# Sheet1.net
KiCad netlist of a schematic drawn in Altium Designer
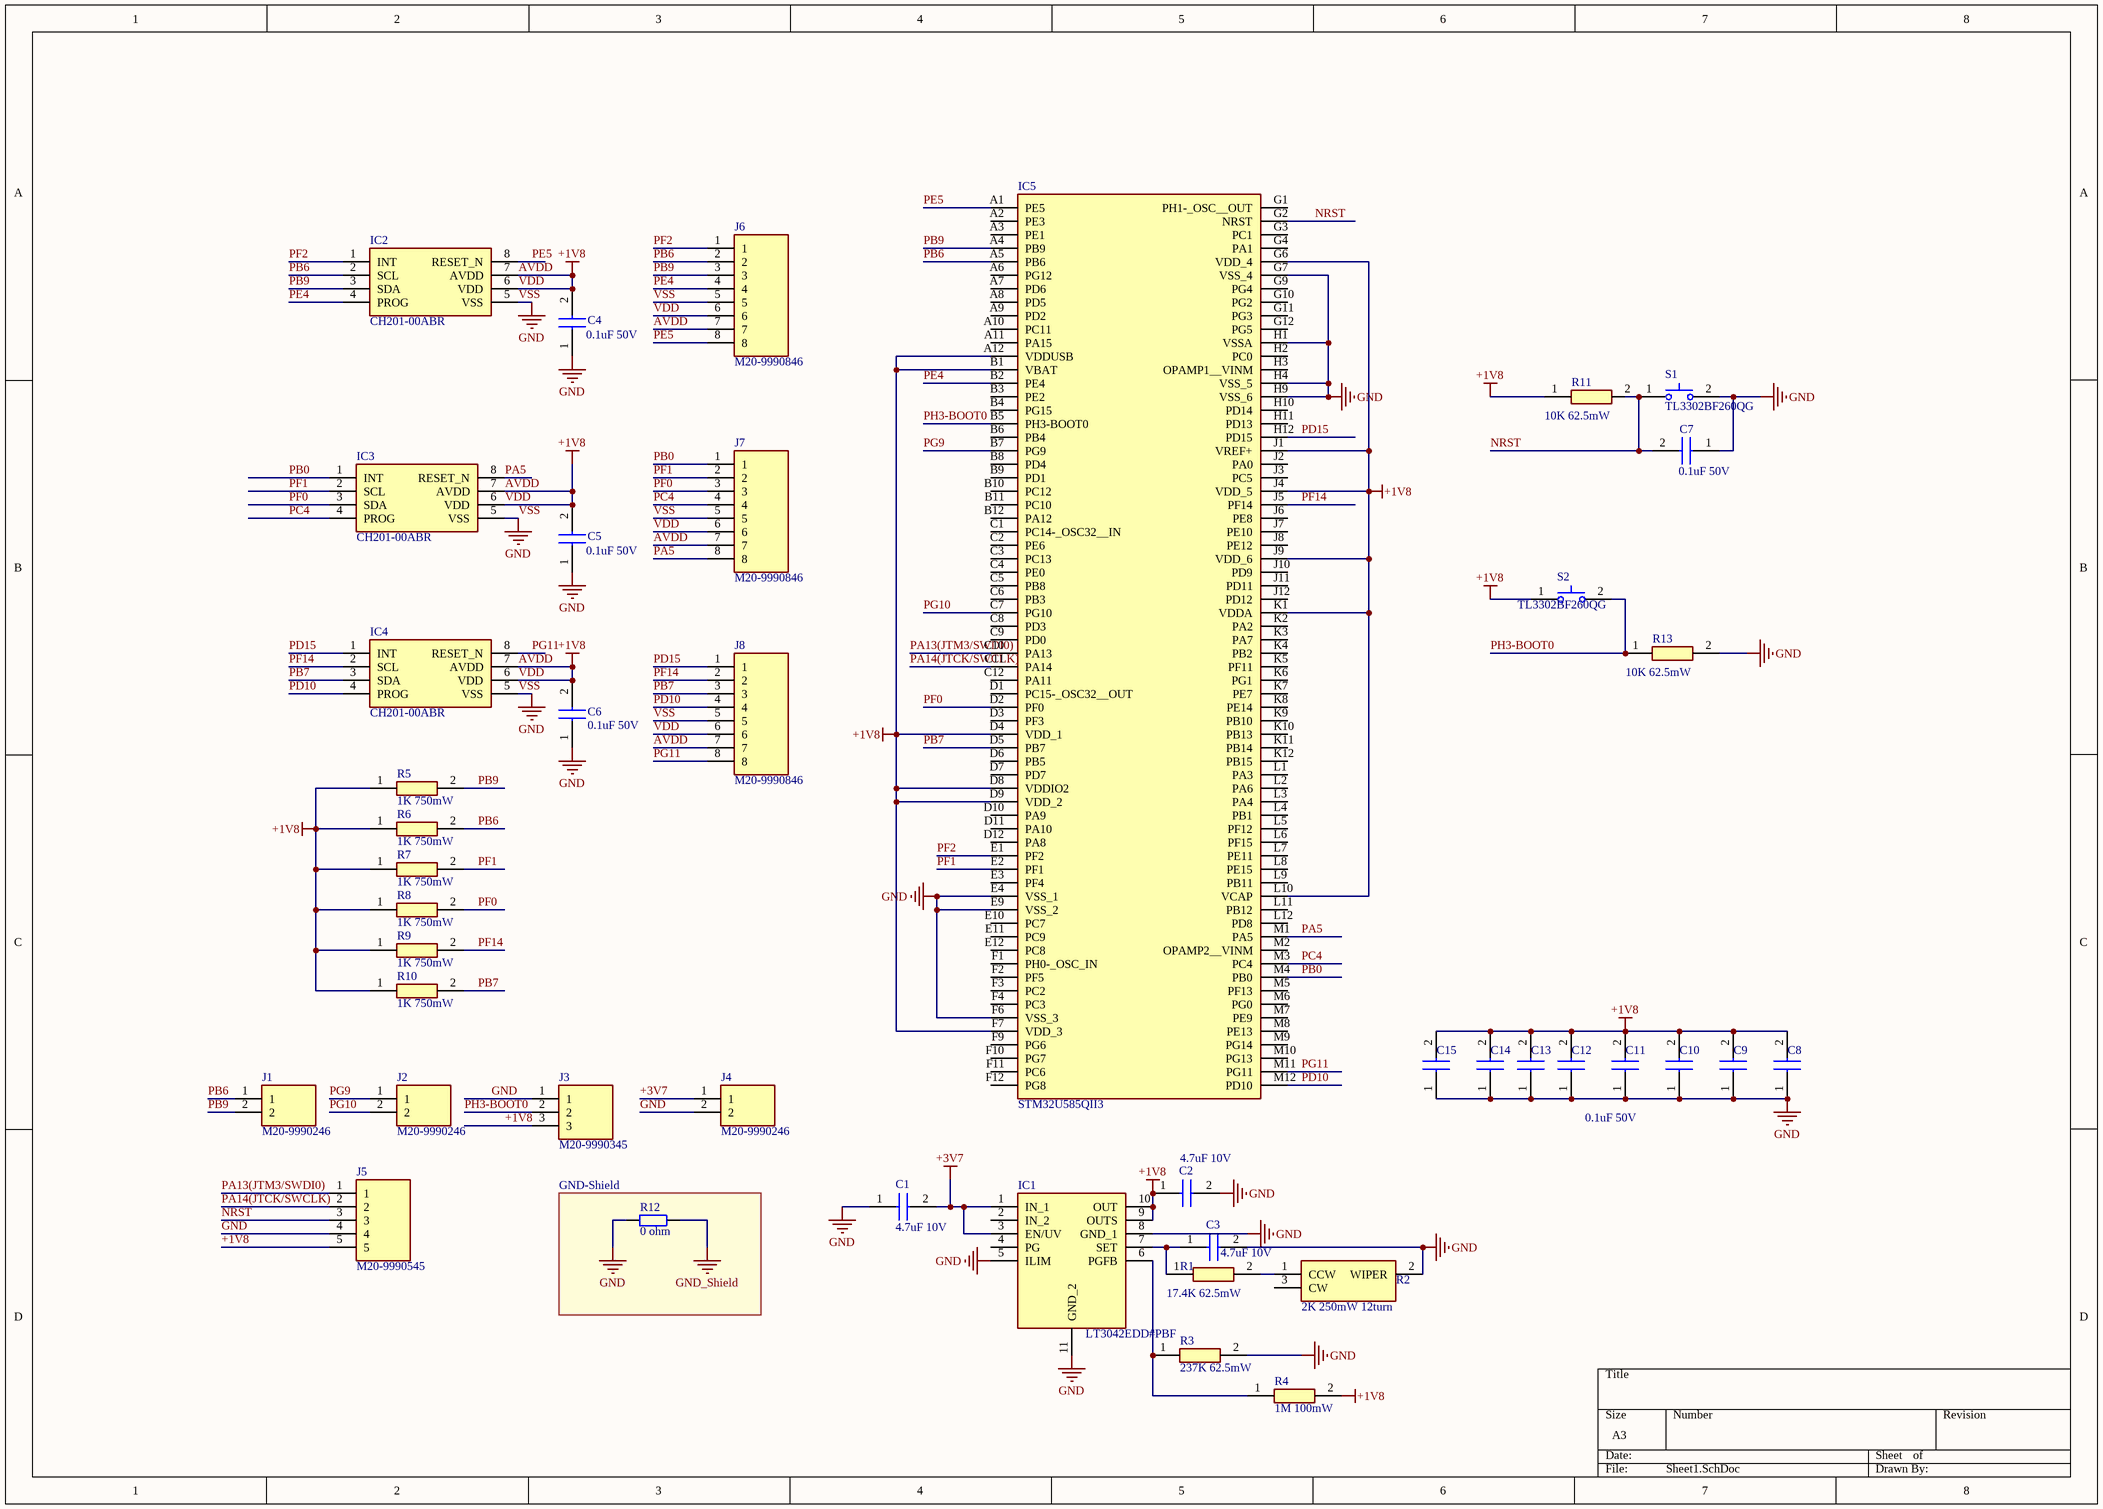
[diagram p0: Sheet1.SchDoc]

(export (version "E")
  (design (tool "Eeschema 10.0.6"))
  (components
    (comp (ref "C1")
      (value "4.7uF 10V")
      (footprint "SamacSys:CAPC3225X220N")
      (description "Capacitor")
      (fields (field (name "MANUFACTURER_PART_NUMBER") "1210X475K100CT"))
      (libsource (lib "*") (part "1210X475K100CT"))
    )
    (comp (ref "C2")
      (value "4.7uF 10V")
      (footprint "SamacSys:CAPC3225X220N")
      (description "Capacitor")
      (fields (field (name "MANUFACTURER_PART_NUMBER") "1210X475K100CT"))
      (libsource (lib "*") (part "1210X475K100CT"))
    )
    (comp (ref "C3")
      (value "4.7uF 10V")
      (footprint "SamacSys:CAPC3225X220N")
      (description "Capacitor")
      (fields (field (name "MANUFACTURER_PART_NUMBER") "1210X475K100CT"))
      (libsource (lib "*") (part "1210X475K100CT"))
    )
    (comp (ref "C4")
      (value "0.1uF 50V")
      (footprint "SamacSys:CAPC1608X90N")
      (description "Capacitor")
      (fields
        (field (name "MANUFACTURER_PART_NUMBER") "CC0603KRX7R9BB104")
        (field (name "MOUSER PART NUMBER") "603-CC603KRX7R9BB104")
      )
      (libsource (lib "SamacSys") (part "CC0603KRX7R9BB104"))
    )
    (comp (ref "C5")
      (value "0.1uF 50V")
      (footprint "SamacSys:CAPC1608X90N")
      (description "Capacitor")
      (fields
        (field (name "MANUFACTURER_PART_NUMBER") "CC0603KRX7R9BB104")
        (field (name "MOUSER PART NUMBER") "603-CC603KRX7R9BB104")
      )
      (libsource (lib "*") (part "CC0603KRX7R9BB104"))
    )
    (comp (ref "C6")
      (value "0.1uF 50V")
      (footprint "SamacSys:CAPC1608X90N")
      (description "Capacitor")
      (fields
        (field (name "MANUFACTURER_PART_NUMBER") "CC0603KRX7R9BB104")
        (field (name "MOUSER PART NUMBER") "603-CC603KRX7R9BB104")
      )
      (libsource (lib "SamacSys") (part "CC0603KRX7R9BB104"))
    )
    (comp (ref "C7")
      (value "0.1uF 50V")
      (footprint "SamacSys:CAPC1608X90N")
      (description "Capacitor")
      (fields
        (field (name "MANUFACTURER_PART_NUMBER") "CC0603KRX7R9BB104")
        (field (name "MOUSER PART NUMBER") "603-CC603KRX7R9BB104")
      )
      (libsource (lib "SamacSys") (part "CC0603KRX7R9BB104"))
    )
    (comp (ref "C8")
      (value "CC0603KRX7R9BB104")
      (footprint "SamacSys:CAPC1608X90N")
      (description "Capacitor")
      (fields (field (name "MOUSER PART NUMBER") "603-CC603KRX7R9BB104"))
      (libsource (lib "SamacSys") (part "CC0603KRX7R9BB104"))
    )
    (comp (ref "C9")
      (value "CC0603KRX7R9BB104")
      (footprint "SamacSys:CAPC1608X90N")
      (description "Capacitor")
      (fields (field (name "MOUSER PART NUMBER") "603-CC603KRX7R9BB104"))
      (libsource (lib "SamacSys") (part "CC0603KRX7R9BB104"))
    )
    (comp (ref "C10")
      (value "CC0603KRX7R9BB104")
      (footprint "SamacSys:CAPC1608X90N")
      (description "Capacitor")
      (fields (field (name "MOUSER PART NUMBER") "603-CC603KRX7R9BB104"))
      (libsource (lib "SamacSys") (part "CC0603KRX7R9BB104"))
    )
    (comp (ref "C11")
      (value "0.1uF 50V")
      (footprint "SamacSys:CAPC1608X90N")
      (description "Capacitor")
      (fields
        (field (name "MANUFACTURER_PART_NUMBER") "CC0603KRX7R9BB104")
        (field (name "MOUSER PART NUMBER") "603-CC603KRX7R9BB104")
      )
      (libsource (lib "SamacSys") (part "CC0603KRX7R9BB104"))
    )
    (comp (ref "C12")
      (value "CC0603KRX7R9BB104")
      (footprint "SamacSys:CAPC1608X90N")
      (description "Capacitor")
      (fields (field (name "MOUSER PART NUMBER") "603-CC603KRX7R9BB104"))
      (libsource (lib "SamacSys") (part "CC0603KRX7R9BB104"))
    )
    (comp (ref "C13")
      (value "CC0603KRX7R9BB104")
      (footprint "SamacSys:CAPC1608X90N")
      (description "Capacitor")
      (fields (field (name "MOUSER PART NUMBER") "603-CC603KRX7R9BB104"))
      (libsource (lib "SamacSys") (part "CC0603KRX7R9BB104"))
    )
    (comp (ref "C14")
      (value "CC0603KRX7R9BB104")
      (footprint "SamacSys:CAPC1608X90N")
      (description "Capacitor")
      (fields (field (name "MOUSER PART NUMBER") "603-CC603KRX7R9BB104"))
      (libsource (lib "SamacSys") (part "CC0603KRX7R9BB104"))
    )
    (comp (ref "C15")
      (value "CC0603KRX7R9BB104")
      (footprint "SamacSys:CAPC1608X90N")
      (description "Capacitor")
      (fields (field (name "MOUSER PART NUMBER") "603-CC603KRX7R9BB104"))
      (libsource (lib "SamacSys") (part "CC0603KRX7R9BB104"))
    )
    (comp (ref "IC1")
      (value "LT3042EDD#PBF")
      (footprint "SamacSys:SON50P300X300X80-11N-D")
      (description "Integrated Circuit")
      (fields (field (name "MOUSER PART NUMBER") "584-LT3042EDD#PBF"))
      (libsource (lib "SamacSys") (part "LT3042EDD#PBF"))
    )
    (comp (ref "IC2")
      (value "CH201-00ABR")
      (footprint "SamacSys:CH20100ABR")
      (description "Filter")
      (fields (field (name "MOUSER PART NUMBER") "410-CH201-00ABR"))
      (libsource (lib "SamacSys") (part "CH201-00ABR"))
    )
    (comp (ref "IC3")
      (value "CH201-00ABR")
      (footprint "SamacSys:CH20100ABR")
      (description "Filter")
      (fields (field (name "MOUSER PART NUMBER") "410-CH201-00ABR"))
      (libsource (lib "SamacSys") (part "CH201-00ABR"))
    )
    (comp (ref "IC4")
      (value "CH201-00ABR")
      (footprint "SamacSys:CH20100ABR")
      (description "Filter")
      (fields (field (name "MOUSER PART NUMBER") "410-CH201-00ABR"))
      (libsource (lib "SamacSys") (part "CH201-00ABR"))
    )
    (comp (ref "IC5")
      (value "STM32U585QII3")
      (footprint "SamacSys:STM32U585QII3")
      (description "Integrated Circuit")
      (fields (field (name "MOUSER PART NUMBER") "511-STM32U585QII3"))
      (libsource (lib "SamacSys") (part "STM32U585QII3"))
    )
    (comp (ref "J1")
      (value "M20-9990246")
      (footprint "SamacSys:HDRV2W66P0X254_1X2_508X254X874P")
      (description "Connector")
      (fields (field (name "MOUSER PART NUMBER") "855-M20-9990246"))
      (libsource (lib "SamacSys") (part "M20-9990246"))
    )
    (comp (ref "J2")
      (value "M20-9990246")
      (footprint "SamacSys:HDRV2W66P0X254_1X2_508X254X874P")
      (description "Connector")
      (fields (field (name "MOUSER PART NUMBER") "855-M20-9990246"))
      (libsource (lib "SamacSys") (part "M20-9990246"))
    )
    (comp (ref "J3")
      (value "M20-9990345")
      (footprint "SamacSys:HDRV3W64P0X254_1X3_762X254X864P")
      (description "Connector")
      (fields (field (name "MOUSER PART NUMBER") "855-M20-9990345"))
      (libsource (lib "SamacSys") (part "M20-9990345"))
    )
    (comp (ref "J4")
      (value "M20-9990246")
      (footprint "SamacSys:HDRV2W66P0X254_1X2_508X254X874P")
      (description "Connector")
      (fields (field (name "MOUSER PART NUMBER") "855-M20-9990246"))
      (libsource (lib "SamacSys") (part "M20-9990246"))
    )
    (comp (ref "J5")
      (value "M20-9990545")
      (footprint "SamacSys:HDRV5W64P0X254_1X5_1270X254X864P")
      (description "Connector")
      (fields (field (name "MOUSER PART NUMBER") "855-M20-9990545"))
      (libsource (lib "*") (part "M20-9990545"))
    )
    (comp (ref "J6")
      (value "M20-9990846")
      (footprint "SamacSys:HDRV8W66P0X254_1X8_2032X254X860P")
      (description "Connector")
      (fields (field (name "MOUSER PART NUMBER") "855-M20-9990846"))
      (libsource (lib "SamacSys") (part "M20-9990846"))
    )
    (comp (ref "J7")
      (value "M20-9990846")
      (footprint "SamacSys:HDRV8W66P0X254_1X8_2032X254X860P")
      (description "Connector")
      (fields (field (name "MOUSER PART NUMBER") "855-M20-9990846"))
      (libsource (lib "SamacSys") (part "M20-9990846"))
    )
    (comp (ref "J8")
      (value "M20-9990846")
      (footprint "SamacSys:HDRV8W66P0X254_1X8_2032X254X860P")
      (description "Connector")
      (fields (field (name "MOUSER PART NUMBER") "855-M20-9990846"))
      (libsource (lib "SamacSys") (part "M20-9990846"))
    )
    (comp (ref "R1")
      (value "17.4K 62.5mW")
      (footprint "SamacSys:RESC1005X40N")
      (description "Resistor")
      (fields
        (field (name "MANUFACTURER_PART_NUMBER") "CR0402-FX-1742GLF")
        (field (name "MOUSER PART NUMBER") "652-CR0402-FX1742GLF")
      )
      (libsource (lib "*") (part "CR0402-FX-1742GLF"))
    )
    (comp (ref "R2")
      (value "2K 250mW 12turn")
      (footprint "SamacSys:3224W1202G")
      (description "Variable Resistor")
      (fields
        (field (name "MANUFACTURER_PART_NUMBER") "3224W-1-202G")
        (field (name "MOUSER PART NUMBER") "652-3224W-1-202G")
      )
      (libsource (lib "*") (part "3224W-1-202G"))
    )
    (comp (ref "R3")
      (value "237K 62.5mW")
      (footprint "SamacSys:RESC1005X40N")
      (description "Resistor")
      (fields
        (field (name "MANUFACTURER_PART_NUMBER") "CR0402-FX-2373GLF")
        (field (name "MOUSER PART NUMBER") "652-CR0402FX2373GLF")
      )
      (libsource (lib "*") (part "CR0402-FX-2373GLF"))
    )
    (comp (ref "R4")
      (value "1M 100mW")
      (footprint "SamacSys:RESC1005X37N")
      (description "Resistor")
      (fields
        (field (name "MANUFACTURER_PART_NUMBER") "MCS0402MD1004BE000")
        (field (name "MOUSER PART NUMBER") "594-MCS0402MD1004BE0")
      )
      (libsource (lib "*") (part "MCS0402MD1004BE000"))
    )
    (comp (ref "R5")
      (value "1K 750mW")
      (footprint "SamacSys:RESC1632X65N")
      (description "Resistor")
      (fields
        (field (name "MANUFACTURER_PART_NUMBER") "LTR18EZPF1001")
        (field (name "MOUSER PART NUMBER") "755-LTR18EZPF1001")
      )
      (libsource (lib "*") (part "LTR18EZPF1001"))
    )
    (comp (ref "R6")
      (value "1K 750mW")
      (footprint "SamacSys:RESC1632X65N")
      (description "Resistor")
      (fields
        (field (name "MANUFACTURER_PART_NUMBER") "LTR18EZPF1001")
        (field (name "MOUSER PART NUMBER") "755-LTR18EZPF1001")
      )
      (libsource (lib "*") (part "LTR18EZPF1001"))
    )
    (comp (ref "R7")
      (value "1K 750mW")
      (footprint "SamacSys:RESC1632X65N")
      (description "Resistor")
      (fields
        (field (name "MANUFACTURER_PART_NUMBER") "LTR18EZPF1001")
        (field (name "MOUSER PART NUMBER") "755-LTR18EZPF1001")
      )
      (libsource (lib "*") (part "LTR18EZPF1001"))
    )
    (comp (ref "R8")
      (value "1K 750mW")
      (footprint "SamacSys:RESC1632X65N")
      (description "Resistor")
      (fields
        (field (name "MANUFACTURER_PART_NUMBER") "LTR18EZPF1001")
        (field (name "MOUSER PART NUMBER") "755-LTR18EZPF1001")
      )
      (libsource (lib "*") (part "LTR18EZPF1001"))
    )
    (comp (ref "R9")
      (value "1K 750mW")
      (footprint "SamacSys:RESC1632X65N")
      (description "Resistor")
      (fields
        (field (name "MANUFACTURER_PART_NUMBER") "LTR18EZPF1001")
        (field (name "MOUSER PART NUMBER") "755-LTR18EZPF1001")
      )
      (libsource (lib "*") (part "LTR18EZPF1001"))
    )
    (comp (ref "R10")
      (value "1K 750mW")
      (footprint "SamacSys:RESC1632X65N")
      (description "Resistor")
      (fields
        (field (name "MANUFACTURER_PART_NUMBER") "LTR18EZPF1001")
        (field (name "MOUSER PART NUMBER") "755-LTR18EZPF1001")
      )
      (libsource (lib "*") (part "LTR18EZPF1001"))
    )
    (comp (ref "R11")
      (value "10K 62.5mW")
      (footprint "SamacSys:RESC1005X40N")
      (description "Resistor")
      (fields
        (field (name "MANUFACTURER_PART_NUMBER") "SFR01MZPF1002")
        (field (name "MOUSER PART NUMBER") "755-SFR01MZPF1002")
      )
      (libsource (lib "*") (part "SFR01MZPF1002"))
    )
    (comp (ref "R12")
      (value "0 ohm")
      (footprint "jumper_2.54")
      (description "Resistor")
      (fields (field (name "PUBLISHER") "Altium Limited"))
      (libsource (lib "Miscellaneous Devices") (part "Res2"))
    )
    (comp (ref "R13")
      (value "10K 62.5mW")
      (footprint "SamacSys:RESC1005X40N")
      (description "Resistor")
      (fields
        (field (name "MANUFACTURER_PART_NUMBER") "SFR01MZPF1002")
        (field (name "MOUSER PART NUMBER") "755-SFR01MZPF1002")
      )
      (libsource (lib "*") (part "SFR01MZPF1002"))
    )
    (comp (ref "S1")
      (value "TL3302BF260QG")
      (footprint "SamacSys:TL3302BF260QG")
      (description "Switch (2-Pin Push)")
      (fields (field (name "MOUSER PART NUMBER") "612-TL3302BF260QG"))
      (libsource (lib "*") (part "TL3302BF260QG"))
    )
    (comp (ref "S2")
      (value "TL3302BF260QG")
      (footprint "SamacSys:TL3302BF260QG")
      (description "Switch (2-Pin Push)")
      (fields (field (name "MOUSER PART NUMBER") "612-TL3302BF260QG"))
      (libsource (lib "*") (part "TL3302BF260QG"))
    )
  )
  (nets
    (net (code "1") (name "+1V8") (class "Default")
      (node (ref "C10") (pin "2") (pinfunction "2_2") (pintype "passive"))
      (node (ref "C11") (pin "2") (pinfunction "2_2") (pintype "passive"))
      (node (ref "C12") (pin "2") (pinfunction "2_2") (pintype "passive"))
      (node (ref "C13") (pin "2") (pinfunction "2_2") (pintype "passive"))
      (node (ref "C14") (pin "2") (pinfunction "2_2") (pintype "passive"))
      (node (ref "C15") (pin "2") (pinfunction "2_2") (pintype "passive"))
      (node (ref "C2") (pin "1") (pinfunction "1_1") (pintype "passive"))
      (node (ref "C4") (pin "2") (pinfunction "2_2") (pintype "passive"))
      (node (ref "C5") (pin "2") (pinfunction "2_2") (pintype "passive"))
      (node (ref "C6") (pin "2") (pinfunction "2_2") (pintype "passive"))
      (node (ref "C8") (pin "2") (pinfunction "2_2") (pintype "passive"))
      (node (ref "C9") (pin "2") (pinfunction "2_2") (pintype "passive"))
      (node (ref "IC1") (pin "10") (pinfunction "OUT_10") (pintype "passive"))
      (node (ref "IC1") (pin "9") (pinfunction "OUTS_9") (pintype "passive"))
      (node (ref "IC2") (pin "6") (pinfunction "VDD_6") (pintype "passive"))
      (node (ref "IC2") (pin "7") (pinfunction "AVDD_7") (pintype "passive"))
      (node (ref "IC3") (pin "6") (pinfunction "VDD_6") (pintype "passive"))
      (node (ref "IC3") (pin "7") (pinfunction "AVDD_7") (pintype "passive"))
      (node (ref "IC4") (pin "6") (pinfunction "VDD_6") (pintype "passive"))
      (node (ref "IC4") (pin "7") (pinfunction "AVDD_7") (pintype "passive"))
      (node (ref "IC5") (pin "A12") (pinfunction "VDDUSB_A12") (pintype "passive"))
      (node (ref "IC5") (pin "B1") (pinfunction "VBAT_B1") (pintype "passive"))
      (node (ref "IC5") (pin "D4") (pinfunction "VDD_1_D4") (pintype "passive"))
      (node (ref "IC5") (pin "D8") (pinfunction "VDDIO2_D8") (pintype "passive"))
      (node (ref "IC5") (pin "D9") (pinfunction "VDD_2_D9") (pintype "passive"))
      (node (ref "IC5") (pin "F7") (pinfunction "VDD_3_F7") (pintype "passive"))
      (node (ref "IC5") (pin "G6") (pinfunction "VDD_4_G6") (pintype "passive"))
      (node (ref "IC5") (pin "J1") (pinfunction "VREF+_J1") (pintype "passive"))
      (node (ref "IC5") (pin "J4") (pinfunction "VDD_5_J4") (pintype "passive"))
      (node (ref "IC5") (pin "J9") (pinfunction "VDD_6_J9") (pintype "passive"))
      (node (ref "IC5") (pin "K1") (pinfunction "VDDA_K1") (pintype "passive"))
      (node (ref "IC5") (pin "L10") (pinfunction "VCAP_L10") (pintype "passive"))
      (node (ref "J3") (pin "3") (pinfunction "3_3") (pintype "passive"))
      (node (ref "J5") (pin "5") (pinfunction "5_5") (pintype "passive"))
      (node (ref "J6") (pin "6") (pinfunction "6_6") (pintype "passive"))
      (node (ref "J6") (pin "7") (pinfunction "7_7") (pintype "passive"))
      (node (ref "J7") (pin "6") (pinfunction "6_6") (pintype "passive"))
      (node (ref "J7") (pin "7") (pinfunction "7_7") (pintype "passive"))
      (node (ref "J8") (pin "6") (pinfunction "6_6") (pintype "passive"))
      (node (ref "J8") (pin "7") (pinfunction "7_7") (pintype "passive"))
      (node (ref "R10") (pin "1") (pinfunction "1_1") (pintype "passive"))
      (node (ref "R11") (pin "1") (pinfunction "1_1") (pintype "passive"))
      (node (ref "R4") (pin "2") (pinfunction "2_2") (pintype "passive"))
      (node (ref "R5") (pin "1") (pinfunction "1_1") (pintype "passive"))
      (node (ref "R6") (pin "1") (pinfunction "1_1") (pintype "passive"))
      (node (ref "R7") (pin "1") (pinfunction "1_1") (pintype "passive"))
      (node (ref "R8") (pin "1") (pinfunction "1_1") (pintype "passive"))
      (node (ref "R9") (pin "1") (pinfunction "1_1") (pintype "passive"))
      (node (ref "S2") (pin "1") (pinfunction "COM_1") (pintype "passive"))
    )
    (net (code "2") (name "+3V7") (class "Default")
      (node (ref "C1") (pin "2") (pinfunction "2_2") (pintype "passive"))
      (node (ref "IC1") (pin "1") (pinfunction "IN_1_1") (pintype "passive"))
      (node (ref "IC1") (pin "3") (pinfunction "EN/UV_3") (pintype "passive"))
      (node (ref "J4") (pin "1") (pinfunction "1_1") (pintype "passive"))
    )
    (net (code "3") (name "/NRST") (class "Default")
      (node (ref "C7") (pin "2") (pinfunction "2_2") (pintype "passive"))
      (node (ref "IC5") (pin "G2") (pinfunction "NRST_G2") (pintype "passive"))
      (node (ref "J5") (pin "3") (pinfunction "3_3") (pintype "passive"))
      (node (ref "R11") (pin "2") (pinfunction "2_2") (pintype "passive"))
      (node (ref "S1") (pin "1") (pinfunction "COM_1") (pintype "passive"))
    )
    (net (code "4") (name "/PA5") (class "Default")
      (node (ref "IC3") (pin "8") (pinfunction "RESET_N_8") (pintype "passive"))
      (node (ref "IC5") (pin "M1") (pinfunction "PA5_M1") (pintype "passive"))
      (node (ref "J7") (pin "8") (pinfunction "8_8") (pintype "passive"))
    )
    (net (code "5") (name "/PA13(JTM3{slash}SWDI0)") (class "Default")
      (node (ref "IC5") (pin "C10") (pinfunction "PA13_C10") (pintype "passive"))
      (node (ref "J5") (pin "1") (pinfunction "1_1") (pintype "passive"))
    )
    (net (code "6") (name "/PA14(JTCK{slash}SWCLK)") (class "Default")
      (node (ref "IC5") (pin "C11") (pinfunction "PA14_C11") (pintype "passive"))
      (node (ref "J5") (pin "2") (pinfunction "2_2") (pintype "passive"))
    )
    (net (code "7") (name "/PB0") (class "Default")
      (node (ref "IC3") (pin "1") (pinfunction "INT_1") (pintype "passive"))
      (node (ref "IC5") (pin "M4") (pinfunction "PB0_M4") (pintype "passive"))
      (node (ref "J7") (pin "1") (pinfunction "1_1") (pintype "passive"))
    )
    (net (code "8") (name "/PB6") (class "Default")
      (node (ref "IC2") (pin "2") (pinfunction "SCL_2") (pintype "passive"))
      (node (ref "IC5") (pin "A5") (pinfunction "PB6_A5") (pintype "passive"))
      (node (ref "J1") (pin "1") (pinfunction "1_1") (pintype "passive"))
      (node (ref "J6") (pin "2") (pinfunction "2_2") (pintype "passive"))
      (node (ref "R6") (pin "2") (pinfunction "2_2") (pintype "passive"))
    )
    (net (code "9") (name "/PB7") (class "Default")
      (node (ref "IC4") (pin "3") (pinfunction "SDA_3") (pintype "passive"))
      (node (ref "IC5") (pin "D5") (pinfunction "PB7_D5") (pintype "passive"))
      (node (ref "J8") (pin "3") (pinfunction "3_3") (pintype "passive"))
      (node (ref "R10") (pin "2") (pinfunction "2_2") (pintype "passive"))
    )
    (net (code "10") (name "/PB9") (class "Default")
      (node (ref "IC2") (pin "3") (pinfunction "SDA_3") (pintype "passive"))
      (node (ref "IC5") (pin "A4") (pinfunction "PB9_A4") (pintype "passive"))
      (node (ref "J1") (pin "2") (pinfunction "2_2") (pintype "passive"))
      (node (ref "J6") (pin "3") (pinfunction "3_3") (pintype "passive"))
      (node (ref "R5") (pin "2") (pinfunction "2_2") (pintype "passive"))
    )
    (net (code "11") (name "/PC4") (class "Default")
      (node (ref "IC3") (pin "4") (pinfunction "PROG_4") (pintype "passive"))
      (node (ref "IC5") (pin "M3") (pinfunction "PC4_M3") (pintype "passive"))
      (node (ref "J7") (pin "4") (pinfunction "4_4") (pintype "passive"))
    )
    (net (code "12") (name "/PD10") (class "Default")
      (node (ref "IC4") (pin "4") (pinfunction "PROG_4") (pintype "passive"))
      (node (ref "IC5") (pin "M12") (pinfunction "PD10_M12") (pintype "passive"))
      (node (ref "J8") (pin "4") (pinfunction "4_4") (pintype "passive"))
    )
    (net (code "13") (name "/PD15") (class "Default")
      (node (ref "IC4") (pin "1") (pinfunction "INT_1") (pintype "passive"))
      (node (ref "IC5") (pin "H12") (pinfunction "PD15_H12") (pintype "passive"))
      (node (ref "J8") (pin "1") (pinfunction "1_1") (pintype "passive"))
    )
    (net (code "14") (name "/PE4") (class "Default")
      (node (ref "IC2") (pin "4") (pinfunction "PROG_4") (pintype "passive"))
      (node (ref "IC5") (pin "B2") (pinfunction "PE4_B2") (pintype "passive"))
      (node (ref "J6") (pin "4") (pinfunction "4_4") (pintype "passive"))
    )
    (net (code "15") (name "/PE5") (class "Default")
      (node (ref "IC2") (pin "8") (pinfunction "RESET_N_8") (pintype "passive"))
      (node (ref "IC5") (pin "A1") (pinfunction "PE5_A1") (pintype "passive"))
      (node (ref "J6") (pin "8") (pinfunction "8_8") (pintype "passive"))
    )
    (net (code "16") (name "/PF0") (class "Default")
      (node (ref "IC3") (pin "3") (pinfunction "SDA_3") (pintype "passive"))
      (node (ref "IC5") (pin "D2") (pinfunction "PF0_D2") (pintype "passive"))
      (node (ref "J7") (pin "3") (pinfunction "3_3") (pintype "passive"))
      (node (ref "R8") (pin "2") (pinfunction "2_2") (pintype "passive"))
    )
    (net (code "17") (name "/PF1") (class "Default")
      (node (ref "IC3") (pin "2") (pinfunction "SCL_2") (pintype "passive"))
      (node (ref "IC5") (pin "E2") (pinfunction "PF1_E2") (pintype "passive"))
      (node (ref "J7") (pin "2") (pinfunction "2_2") (pintype "passive"))
      (node (ref "R7") (pin "2") (pinfunction "2_2") (pintype "passive"))
    )
    (net (code "18") (name "/PF2") (class "Default")
      (node (ref "IC2") (pin "1") (pinfunction "INT_1") (pintype "passive"))
      (node (ref "IC5") (pin "E1") (pinfunction "PF2_E1") (pintype "passive"))
      (node (ref "J6") (pin "1") (pinfunction "1_1") (pintype "passive"))
    )
    (net (code "19") (name "/PF14") (class "Default")
      (node (ref "IC4") (pin "2") (pinfunction "SCL_2") (pintype "passive"))
      (node (ref "IC5") (pin "J5") (pinfunction "PF14_J5") (pintype "passive"))
      (node (ref "J8") (pin "2") (pinfunction "2_2") (pintype "passive"))
      (node (ref "R9") (pin "2") (pinfunction "2_2") (pintype "passive"))
    )
    (net (code "20") (name "/PG9") (class "Default")
      (node (ref "IC5") (pin "B7") (pinfunction "PG9_B7") (pintype "passive"))
      (node (ref "J2") (pin "1") (pinfunction "1_1") (pintype "passive"))
    )
    (net (code "21") (name "/PG10") (class "Default")
      (node (ref "IC5") (pin "C7") (pinfunction "PG10_C7") (pintype "passive"))
      (node (ref "J2") (pin "2") (pinfunction "2_2") (pintype "passive"))
    )
    (net (code "22") (name "/PG11") (class "Default")
      (node (ref "IC4") (pin "8") (pinfunction "RESET_N_8") (pintype "passive"))
      (node (ref "IC5") (pin "M11") (pinfunction "PG11_M11") (pintype "passive"))
      (node (ref "J8") (pin "8") (pinfunction "8_8") (pintype "passive"))
    )
    (net (code "23") (name "/PH3-BOOT0") (class "Default")
      (node (ref "IC5") (pin "B5") (pinfunction "PH3-BOOT0_B5") (pintype "passive"))
      (node (ref "J3") (pin "2") (pinfunction "2_2") (pintype "passive"))
      (node (ref "R13") (pin "1") (pinfunction "1_1") (pintype "passive"))
      (node (ref "S2") (pin "2") (pinfunction "NO_2") (pintype "passive"))
    )
    (net (code "24") (name "GND") (class "Default")
      (node (ref "C1") (pin "1") (pinfunction "1_1") (pintype "passive"))
      (node (ref "C10") (pin "1") (pinfunction "1_1") (pintype "passive"))
      (node (ref "C11") (pin "1") (pinfunction "1_1") (pintype "passive"))
      (node (ref "C12") (pin "1") (pinfunction "1_1") (pintype "passive"))
      (node (ref "C13") (pin "1") (pinfunction "1_1") (pintype "passive"))
      (node (ref "C14") (pin "1") (pinfunction "1_1") (pintype "passive"))
      (node (ref "C15") (pin "1") (pinfunction "1_1") (pintype "passive"))
      (node (ref "C2") (pin "2") (pinfunction "2_2") (pintype "passive"))
      (node (ref "C3") (pin "2") (pinfunction "2_2") (pintype "passive"))
      (node (ref "C4") (pin "1") (pinfunction "1_1") (pintype "passive"))
      (node (ref "C5") (pin "1") (pinfunction "1_1") (pintype "passive"))
      (node (ref "C6") (pin "1") (pinfunction "1_1") (pintype "passive"))
      (node (ref "C7") (pin "1") (pinfunction "1_1") (pintype "passive"))
      (node (ref "C8") (pin "1") (pinfunction "1_1") (pintype "passive"))
      (node (ref "C9") (pin "1") (pinfunction "1_1") (pintype "passive"))
      (node (ref "IC1") (pin "11") (pinfunction "GND_2_11") (pintype "passive"))
      (node (ref "IC1") (pin "5") (pinfunction "ILIM_5") (pintype "passive"))
      (node (ref "IC1") (pin "8") (pinfunction "GND_1_8") (pintype "passive"))
      (node (ref "IC2") (pin "5") (pinfunction "VSS_5") (pintype "passive"))
      (node (ref "IC3") (pin "5") (pinfunction "VSS_5") (pintype "passive"))
      (node (ref "IC4") (pin "5") (pinfunction "VSS_5") (pintype "passive"))
      (node (ref "IC5") (pin "E4") (pinfunction "VSS_1_E4") (pintype "passive"))
      (node (ref "IC5") (pin "E9") (pinfunction "VSS_2_E9") (pintype "passive"))
      (node (ref "IC5") (pin "F6") (pinfunction "VSS_3_F6") (pintype "passive"))
      (node (ref "IC5") (pin "G7") (pinfunction "VSS_4_G7") (pintype "passive"))
      (node (ref "IC5") (pin "H1") (pinfunction "VSSA_H1") (pintype "passive"))
      (node (ref "IC5") (pin "H4") (pinfunction "VSS_5_H4") (pintype "passive"))
      (node (ref "IC5") (pin "H9") (pinfunction "VSS_6_H9") (pintype "passive"))
      (node (ref "J3") (pin "1") (pinfunction "1_1") (pintype "passive"))
      (node (ref "J4") (pin "2") (pinfunction "2_2") (pintype "passive"))
      (node (ref "J5") (pin "4") (pinfunction "4_4") (pintype "passive"))
      (node (ref "J6") (pin "5") (pinfunction "5_5") (pintype "passive"))
      (node (ref "J7") (pin "5") (pinfunction "5_5") (pintype "passive"))
      (node (ref "J8") (pin "5") (pinfunction "5_5") (pintype "passive"))
      (node (ref "R12") (pin "2") (pinfunction "2_2") (pintype "passive"))
      (node (ref "R13") (pin "2") (pinfunction "2_2") (pintype "passive"))
      (node (ref "R2") (pin "2") (pinfunction "WIPER_2") (pintype "passive"))
      (node (ref "R3") (pin "2") (pinfunction "2_2") (pintype "passive"))
      (node (ref "S1") (pin "2") (pinfunction "NO_2") (pintype "passive"))
    )
    (net (code "25") (name "GND_Shield") (class "Default")
      (node (ref "R12") (pin "1") (pinfunction "1_1") (pintype "passive"))
    )
    (net (code "26") (name "Net-(IC1-PGFB)") (class "Default")
      (node (ref "IC1") (pin "6") (pinfunction "PGFB_6") (pintype "passive"))
      (node (ref "R3") (pin "1") (pinfunction "1_1") (pintype "passive"))
      (node (ref "R4") (pin "1") (pinfunction "1_1") (pintype "passive"))
    )
    (net (code "27") (name "Net-(IC1-SET)") (class "Default")
      (node (ref "C3") (pin "1") (pinfunction "1_1") (pintype "passive"))
      (node (ref "IC1") (pin "7") (pinfunction "SET_7") (pintype "passive"))
      (node (ref "R1") (pin "1") (pinfunction "1_1") (pintype "passive"))
    )
    (net (code "28") (name "Net-(R2-CCW)") (class "Default")
      (node (ref "R1") (pin "2") (pinfunction "2_2") (pintype "passive"))
      (node (ref "R2") (pin "1") (pinfunction "CCW_1") (pintype "passive"))
    )
    (net (code "29") (name "unconnected-(IC1-IN_2-Pad2)") (class "Default")
      (node (ref "IC1") (pin "2") (pinfunction "IN_2_2") (pintype "passive"))
    )
    (net (code "30") (name "unconnected-(IC1-PG-Pad4)") (class "Default")
      (node (ref "IC1") (pin "4") (pinfunction "PG_4") (pintype "passive"))
    )
    (net (code "31") (name "unconnected-(IC5-OPAMP1__VINM-PadH3)") (class "Default")
      (node (ref "IC5") (pin "H3") (pinfunction "OPAMP1__VINM_H3") (pintype "passive"))
    )
    (net (code "32") (name "unconnected-(IC5-OPAMP2__VINM-PadM2)") (class "Default")
      (node (ref "IC5") (pin "M2") (pinfunction "OPAMP2__VINM_M2") (pintype "passive"))
    )
    (net (code "33") (name "unconnected-(IC5-PA0-PadJ2)") (class "Default")
      (node (ref "IC5") (pin "J2") (pinfunction "PA0_J2") (pintype "passive"))
    )
    (net (code "34") (name "unconnected-(IC5-PA1-PadG4)") (class "Default")
      (node (ref "IC5") (pin "G4") (pinfunction "PA1_G4") (pintype "passive"))
    )
    (net (code "35") (name "unconnected-(IC5-PA2-PadK2)") (class "Default")
      (node (ref "IC5") (pin "K2") (pinfunction "PA2_K2") (pintype "passive"))
    )
    (net (code "36") (name "unconnected-(IC5-PA3-PadL1)") (class "Default")
      (node (ref "IC5") (pin "L1") (pinfunction "PA3_L1") (pintype "passive"))
    )
    (net (code "37") (name "unconnected-(IC5-PA4-PadL3)") (class "Default")
      (node (ref "IC5") (pin "L3") (pinfunction "PA4_L3") (pintype "passive"))
    )
    (net (code "38") (name "unconnected-(IC5-PA6-PadL2)") (class "Default")
      (node (ref "IC5") (pin "L2") (pinfunction "PA6_L2") (pintype "passive"))
    )
    (net (code "39") (name "unconnected-(IC5-PA7-PadK3)") (class "Default")
      (node (ref "IC5") (pin "K3") (pinfunction "PA7_K3") (pintype "passive"))
    )
    (net (code "40") (name "unconnected-(IC5-PA8-PadD12)") (class "Default")
      (node (ref "IC5") (pin "D12") (pinfunction "PA8_D12") (pintype "passive"))
    )
    (net (code "41") (name "unconnected-(IC5-PA9-PadD10)") (class "Default")
      (node (ref "IC5") (pin "D10") (pinfunction "PA9_D10") (pintype "passive"))
    )
    (net (code "42") (name "unconnected-(IC5-PA10-PadD11)") (class "Default")
      (node (ref "IC5") (pin "D11") (pinfunction "PA10_D11") (pintype "passive"))
    )
    (net (code "43") (name "unconnected-(IC5-PA11-PadC12)") (class "Default")
      (node (ref "IC5") (pin "C12") (pinfunction "PA11_C12") (pintype "passive"))
    )
    (net (code "44") (name "unconnected-(IC5-PA12-PadB12)") (class "Default")
      (node (ref "IC5") (pin "B12") (pinfunction "PA12_B12") (pintype "passive"))
    )
    (net (code "45") (name "unconnected-(IC5-PA15-PadA11)") (class "Default")
      (node (ref "IC5") (pin "A11") (pinfunction "PA15_A11") (pintype "passive"))
    )
    (net (code "46") (name "unconnected-(IC5-PB1-PadL4)") (class "Default")
      (node (ref "IC5") (pin "L4") (pinfunction "PB1_L4") (pintype "passive"))
    )
    (net (code "47") (name "unconnected-(IC5-PB2-PadK4)") (class "Default")
      (node (ref "IC5") (pin "K4") (pinfunction "PB2_K4") (pintype "passive"))
    )
    (net (code "48") (name "unconnected-(IC5-PB3-PadC6)") (class "Default")
      (node (ref "IC5") (pin "C6") (pinfunction "PB3_C6") (pintype "passive"))
    )
    (net (code "49") (name "unconnected-(IC5-PB4-PadB6)") (class "Default")
      (node (ref "IC5") (pin "B6") (pinfunction "PB4_B6") (pintype "passive"))
    )
    (net (code "50") (name "unconnected-(IC5-PB5-PadD6)") (class "Default")
      (node (ref "IC5") (pin "D6") (pinfunction "PB5_D6") (pintype "passive"))
    )
    (net (code "51") (name "unconnected-(IC5-PB8-PadC5)") (class "Default")
      (node (ref "IC5") (pin "C5") (pinfunction "PB8_C5") (pintype "passive"))
    )
    (net (code "52") (name "unconnected-(IC5-PB10-PadK9)") (class "Default")
      (node (ref "IC5") (pin "K9") (pinfunction "PB10_K9") (pintype "passive"))
    )
    (net (code "53") (name "unconnected-(IC5-PB11-PadL9)") (class "Default")
      (node (ref "IC5") (pin "L9") (pinfunction "PB11_L9") (pintype "passive"))
    )
    (net (code "54") (name "unconnected-(IC5-PB12-PadL11)") (class "Default")
      (node (ref "IC5") (pin "L11") (pinfunction "PB12_L11") (pintype "passive"))
    )
    (net (code "55") (name "unconnected-(IC5-PB13-PadK10)") (class "Default")
      (node (ref "IC5") (pin "K10") (pinfunction "PB13_K10") (pintype "passive"))
    )
    (net (code "56") (name "unconnected-(IC5-PB14-PadK11)") (class "Default")
      (node (ref "IC5") (pin "K11") (pinfunction "PB14_K11") (pintype "passive"))
    )
    (net (code "57") (name "unconnected-(IC5-PB15-PadK12)") (class "Default")
      (node (ref "IC5") (pin "K12") (pinfunction "PB15_K12") (pintype "passive"))
    )
    (net (code "58") (name "unconnected-(IC5-PC0-PadH2)") (class "Default")
      (node (ref "IC5") (pin "H2") (pinfunction "PC0_H2") (pintype "passive"))
    )
    (net (code "59") (name "unconnected-(IC5-PC1-PadG3)") (class "Default")
      (node (ref "IC5") (pin "G3") (pinfunction "PC1_G3") (pintype "passive"))
    )
    (net (code "60") (name "unconnected-(IC5-PC2-PadF3)") (class "Default")
      (node (ref "IC5") (pin "F3") (pinfunction "PC2_F3") (pintype "passive"))
    )
    (net (code "61") (name "unconnected-(IC5-PC3-PadF4)") (class "Default")
      (node (ref "IC5") (pin "F4") (pinfunction "PC3_F4") (pintype "passive"))
    )
    (net (code "62") (name "unconnected-(IC5-PC5-PadJ3)") (class "Default")
      (node (ref "IC5") (pin "J3") (pinfunction "PC5_J3") (pintype "passive"))
    )
    (net (code "63") (name "unconnected-(IC5-PC6-PadF11)") (class "Default")
      (node (ref "IC5") (pin "F11") (pinfunction "PC6_F11") (pintype "passive"))
    )
    (net (code "64") (name "unconnected-(IC5-PC7-PadE10)") (class "Default")
      (node (ref "IC5") (pin "E10") (pinfunction "PC7_E10") (pintype "passive"))
    )
    (net (code "65") (name "unconnected-(IC5-PC8-PadE12)") (class "Default")
      (node (ref "IC5") (pin "E12") (pinfunction "PC8_E12") (pintype "passive"))
    )
    (net (code "66") (name "unconnected-(IC5-PC9-PadE11)") (class "Default")
      (node (ref "IC5") (pin "E11") (pinfunction "PC9_E11") (pintype "passive"))
    )
    (net (code "67") (name "unconnected-(IC5-PC10-PadB11)") (class "Default")
      (node (ref "IC5") (pin "B11") (pinfunction "PC10_B11") (pintype "passive"))
    )
    (net (code "68") (name "unconnected-(IC5-PC11-PadA10)") (class "Default")
      (node (ref "IC5") (pin "A10") (pinfunction "PC11_A10") (pintype "passive"))
    )
    (net (code "69") (name "unconnected-(IC5-PC12-PadB10)") (class "Default")
      (node (ref "IC5") (pin "B10") (pinfunction "PC12_B10") (pintype "passive"))
    )
    (net (code "70") (name "unconnected-(IC5-PC13-PadC3)") (class "Default")
      (node (ref "IC5") (pin "C3") (pinfunction "PC13_C3") (pintype "passive"))
    )
    (net (code "71") (name "unconnected-(IC5-PC14-_OSC32__IN-PadC1)") (class "Default")
      (node (ref "IC5") (pin "C1") (pinfunction "PC14-_OSC32__IN_C1") (pintype "passive"))
    )
    (net (code "72") (name "unconnected-(IC5-PC15-_OSC32__OUT-PadD1)") (class "Default")
      (node (ref "IC5") (pin "D1") (pinfunction "PC15-_OSC32__OUT_D1") (pintype "passive"))
    )
    (net (code "73") (name "unconnected-(IC5-PD0-PadC9)") (class "Default")
      (node (ref "IC5") (pin "C9") (pinfunction "PD0_C9") (pintype "passive"))
    )
    (net (code "74") (name "unconnected-(IC5-PD1-PadB9)") (class "Default")
      (node (ref "IC5") (pin "B9") (pinfunction "PD1_B9") (pintype "passive"))
    )
    (net (code "75") (name "unconnected-(IC5-PD2-PadA9)") (class "Default")
      (node (ref "IC5") (pin "A9") (pinfunction "PD2_A9") (pintype "passive"))
    )
    (net (code "76") (name "unconnected-(IC5-PD3-PadC8)") (class "Default")
      (node (ref "IC5") (pin "C8") (pinfunction "PD3_C8") (pintype "passive"))
    )
    (net (code "77") (name "unconnected-(IC5-PD4-PadB8)") (class "Default")
      (node (ref "IC5") (pin "B8") (pinfunction "PD4_B8") (pintype "passive"))
    )
    (net (code "78") (name "unconnected-(IC5-PD5-PadA8)") (class "Default")
      (node (ref "IC5") (pin "A8") (pinfunction "PD5_A8") (pintype "passive"))
    )
    (net (code "79") (name "unconnected-(IC5-PD6-PadA7)") (class "Default")
      (node (ref "IC5") (pin "A7") (pinfunction "PD6_A7") (pintype "passive"))
    )
    (net (code "80") (name "unconnected-(IC5-PD7-PadD7)") (class "Default")
      (node (ref "IC5") (pin "D7") (pinfunction "PD7_D7") (pintype "passive"))
    )
    (net (code "81") (name "unconnected-(IC5-PD8-PadL12)") (class "Default")
      (node (ref "IC5") (pin "L12") (pinfunction "PD8_L12") (pintype "passive"))
    )
    (net (code "82") (name "unconnected-(IC5-PD9-PadJ10)") (class "Default")
      (node (ref "IC5") (pin "J10") (pinfunction "PD9_J10") (pintype "passive"))
    )
    (net (code "83") (name "unconnected-(IC5-PD11-PadJ11)") (class "Default")
      (node (ref "IC5") (pin "J11") (pinfunction "PD11_J11") (pintype "passive"))
    )
    (net (code "84") (name "unconnected-(IC5-PD12-PadJ12)") (class "Default")
      (node (ref "IC5") (pin "J12") (pinfunction "PD12_J12") (pintype "passive"))
    )
    (net (code "85") (name "unconnected-(IC5-PD13-PadH11)") (class "Default")
      (node (ref "IC5") (pin "H11") (pinfunction "PD13_H11") (pintype "passive"))
    )
    (net (code "86") (name "unconnected-(IC5-PD14-PadH10)") (class "Default")
      (node (ref "IC5") (pin "H10") (pinfunction "PD14_H10") (pintype "passive"))
    )
    (net (code "87") (name "unconnected-(IC5-PE0-PadC4)") (class "Default")
      (node (ref "IC5") (pin "C4") (pinfunction "PE0_C4") (pintype "passive"))
    )
    (net (code "88") (name "unconnected-(IC5-PE1-PadA3)") (class "Default")
      (node (ref "IC5") (pin "A3") (pinfunction "PE1_A3") (pintype "passive"))
    )
    (net (code "89") (name "unconnected-(IC5-PE2-PadB3)") (class "Default")
      (node (ref "IC5") (pin "B3") (pinfunction "PE2_B3") (pintype "passive"))
    )
    (net (code "90") (name "unconnected-(IC5-PE3-PadA2)") (class "Default")
      (node (ref "IC5") (pin "A2") (pinfunction "PE3_A2") (pintype "passive"))
    )
    (net (code "91") (name "unconnected-(IC5-PE6-PadC2)") (class "Default")
      (node (ref "IC5") (pin "C2") (pinfunction "PE6_C2") (pintype "passive"))
    )
    (net (code "92") (name "unconnected-(IC5-PE7-PadK7)") (class "Default")
      (node (ref "IC5") (pin "K7") (pinfunction "PE7_K7") (pintype "passive"))
    )
    (net (code "93") (name "unconnected-(IC5-PE8-PadJ6)") (class "Default")
      (node (ref "IC5") (pin "J6") (pinfunction "PE8_J6") (pintype "passive"))
    )
    (net (code "94") (name "unconnected-(IC5-PE9-PadM7)") (class "Default")
      (node (ref "IC5") (pin "M7") (pinfunction "PE9_M7") (pintype "passive"))
    )
    (net (code "95") (name "unconnected-(IC5-PE10-PadJ7)") (class "Default")
      (node (ref "IC5") (pin "J7") (pinfunction "PE10_J7") (pintype "passive"))
    )
    (net (code "96") (name "unconnected-(IC5-PE11-PadL7)") (class "Default")
      (node (ref "IC5") (pin "L7") (pinfunction "PE11_L7") (pintype "passive"))
    )
    (net (code "97") (name "unconnected-(IC5-PE12-PadJ8)") (class "Default")
      (node (ref "IC5") (pin "J8") (pinfunction "PE12_J8") (pintype "passive"))
    )
    (net (code "98") (name "unconnected-(IC5-PE13-PadM8)") (class "Default")
      (node (ref "IC5") (pin "M8") (pinfunction "PE13_M8") (pintype "passive"))
    )
    (net (code "99") (name "unconnected-(IC5-PE14-PadK8)") (class "Default")
      (node (ref "IC5") (pin "K8") (pinfunction "PE14_K8") (pintype "passive"))
    )
    (net (code "100") (name "unconnected-(IC5-PE15-PadL8)") (class "Default")
      (node (ref "IC5") (pin "L8") (pinfunction "PE15_L8") (pintype "passive"))
    )
    (net (code "101") (name "unconnected-(IC5-PF3-PadD3)") (class "Default")
      (node (ref "IC5") (pin "D3") (pinfunction "PF3_D3") (pintype "passive"))
    )
    (net (code "102") (name "unconnected-(IC5-PF4-PadE3)") (class "Default")
      (node (ref "IC5") (pin "E3") (pinfunction "PF4_E3") (pintype "passive"))
    )
    (net (code "103") (name "unconnected-(IC5-PF5-PadF2)") (class "Default")
      (node (ref "IC5") (pin "F2") (pinfunction "PF5_F2") (pintype "passive"))
    )
    (net (code "104") (name "unconnected-(IC5-PF11-PadK5)") (class "Default")
      (node (ref "IC5") (pin "K5") (pinfunction "PF11_K5") (pintype "passive"))
    )
    (net (code "105") (name "unconnected-(IC5-PF12-PadL5)") (class "Default")
      (node (ref "IC5") (pin "L5") (pinfunction "PF12_L5") (pintype "passive"))
    )
    (net (code "106") (name "unconnected-(IC5-PF13-PadM5)") (class "Default")
      (node (ref "IC5") (pin "M5") (pinfunction "PF13_M5") (pintype "passive"))
    )
    (net (code "107") (name "unconnected-(IC5-PF15-PadL6)") (class "Default")
      (node (ref "IC5") (pin "L6") (pinfunction "PF15_L6") (pintype "passive"))
    )
    (net (code "108") (name "unconnected-(IC5-PG0-PadM6)") (class "Default")
      (node (ref "IC5") (pin "M6") (pinfunction "PG0_M6") (pintype "passive"))
    )
    (net (code "109") (name "unconnected-(IC5-PG1-PadK6)") (class "Default")
      (node (ref "IC5") (pin "K6") (pinfunction "PG1_K6") (pintype "passive"))
    )
    (net (code "110") (name "unconnected-(IC5-PG2-PadG10)") (class "Default")
      (node (ref "IC5") (pin "G10") (pinfunction "PG2_G10") (pintype "passive"))
    )
    (net (code "111") (name "unconnected-(IC5-PG3-PadG11)") (class "Default")
      (node (ref "IC5") (pin "G11") (pinfunction "PG3_G11") (pintype "passive"))
    )
    (net (code "112") (name "unconnected-(IC5-PG4-PadG9)") (class "Default")
      (node (ref "IC5") (pin "G9") (pinfunction "PG4_G9") (pintype "passive"))
    )
    (net (code "113") (name "unconnected-(IC5-PG5-PadG12)") (class "Default")
      (node (ref "IC5") (pin "G12") (pinfunction "PG5_G12") (pintype "passive"))
    )
    (net (code "114") (name "unconnected-(IC5-PG6-PadF9)") (class "Default")
      (node (ref "IC5") (pin "F9") (pinfunction "PG6_F9") (pintype "passive"))
    )
    (net (code "115") (name "unconnected-(IC5-PG7-PadF10)") (class "Default")
      (node (ref "IC5") (pin "F10") (pinfunction "PG7_F10") (pintype "passive"))
    )
    (net (code "116") (name "unconnected-(IC5-PG8-PadF12)") (class "Default")
      (node (ref "IC5") (pin "F12") (pinfunction "PG8_F12") (pintype "passive"))
    )
    (net (code "117") (name "unconnected-(IC5-PG12-PadA6)") (class "Default")
      (node (ref "IC5") (pin "A6") (pinfunction "PG12_A6") (pintype "passive"))
    )
    (net (code "118") (name "unconnected-(IC5-PG13-PadM10)") (class "Default")
      (node (ref "IC5") (pin "M10") (pinfunction "PG13_M10") (pintype "passive"))
    )
    (net (code "119") (name "unconnected-(IC5-PG14-PadM9)") (class "Default")
      (node (ref "IC5") (pin "M9") (pinfunction "PG14_M9") (pintype "passive"))
    )
    (net (code "120") (name "unconnected-(IC5-PG15-PadB4)") (class "Default")
      (node (ref "IC5") (pin "B4") (pinfunction "PG15_B4") (pintype "passive"))
    )
    (net (code "121") (name "unconnected-(IC5-PH0-_OSC_IN-PadF1)") (class "Default")
      (node (ref "IC5") (pin "F1") (pinfunction "PH0-_OSC_IN_F1") (pintype "passive"))
    )
    (net (code "122") (name "unconnected-(IC5-PH1-_OSC__OUT-PadG1)") (class "Default")
      (node (ref "IC5") (pin "G1") (pinfunction "PH1-_OSC__OUT_G1") (pintype "passive"))
    )
    (net (code "123") (name "unconnected-(R2-CW-Pad3)") (class "Default")
      (node (ref "R2") (pin "3") (pinfunction "CW_3") (pintype "passive"))
    )
  )
)
